# Speaker_Switch_2.net
KiCad netlist of a schematic drawn in EasyEDA Pro
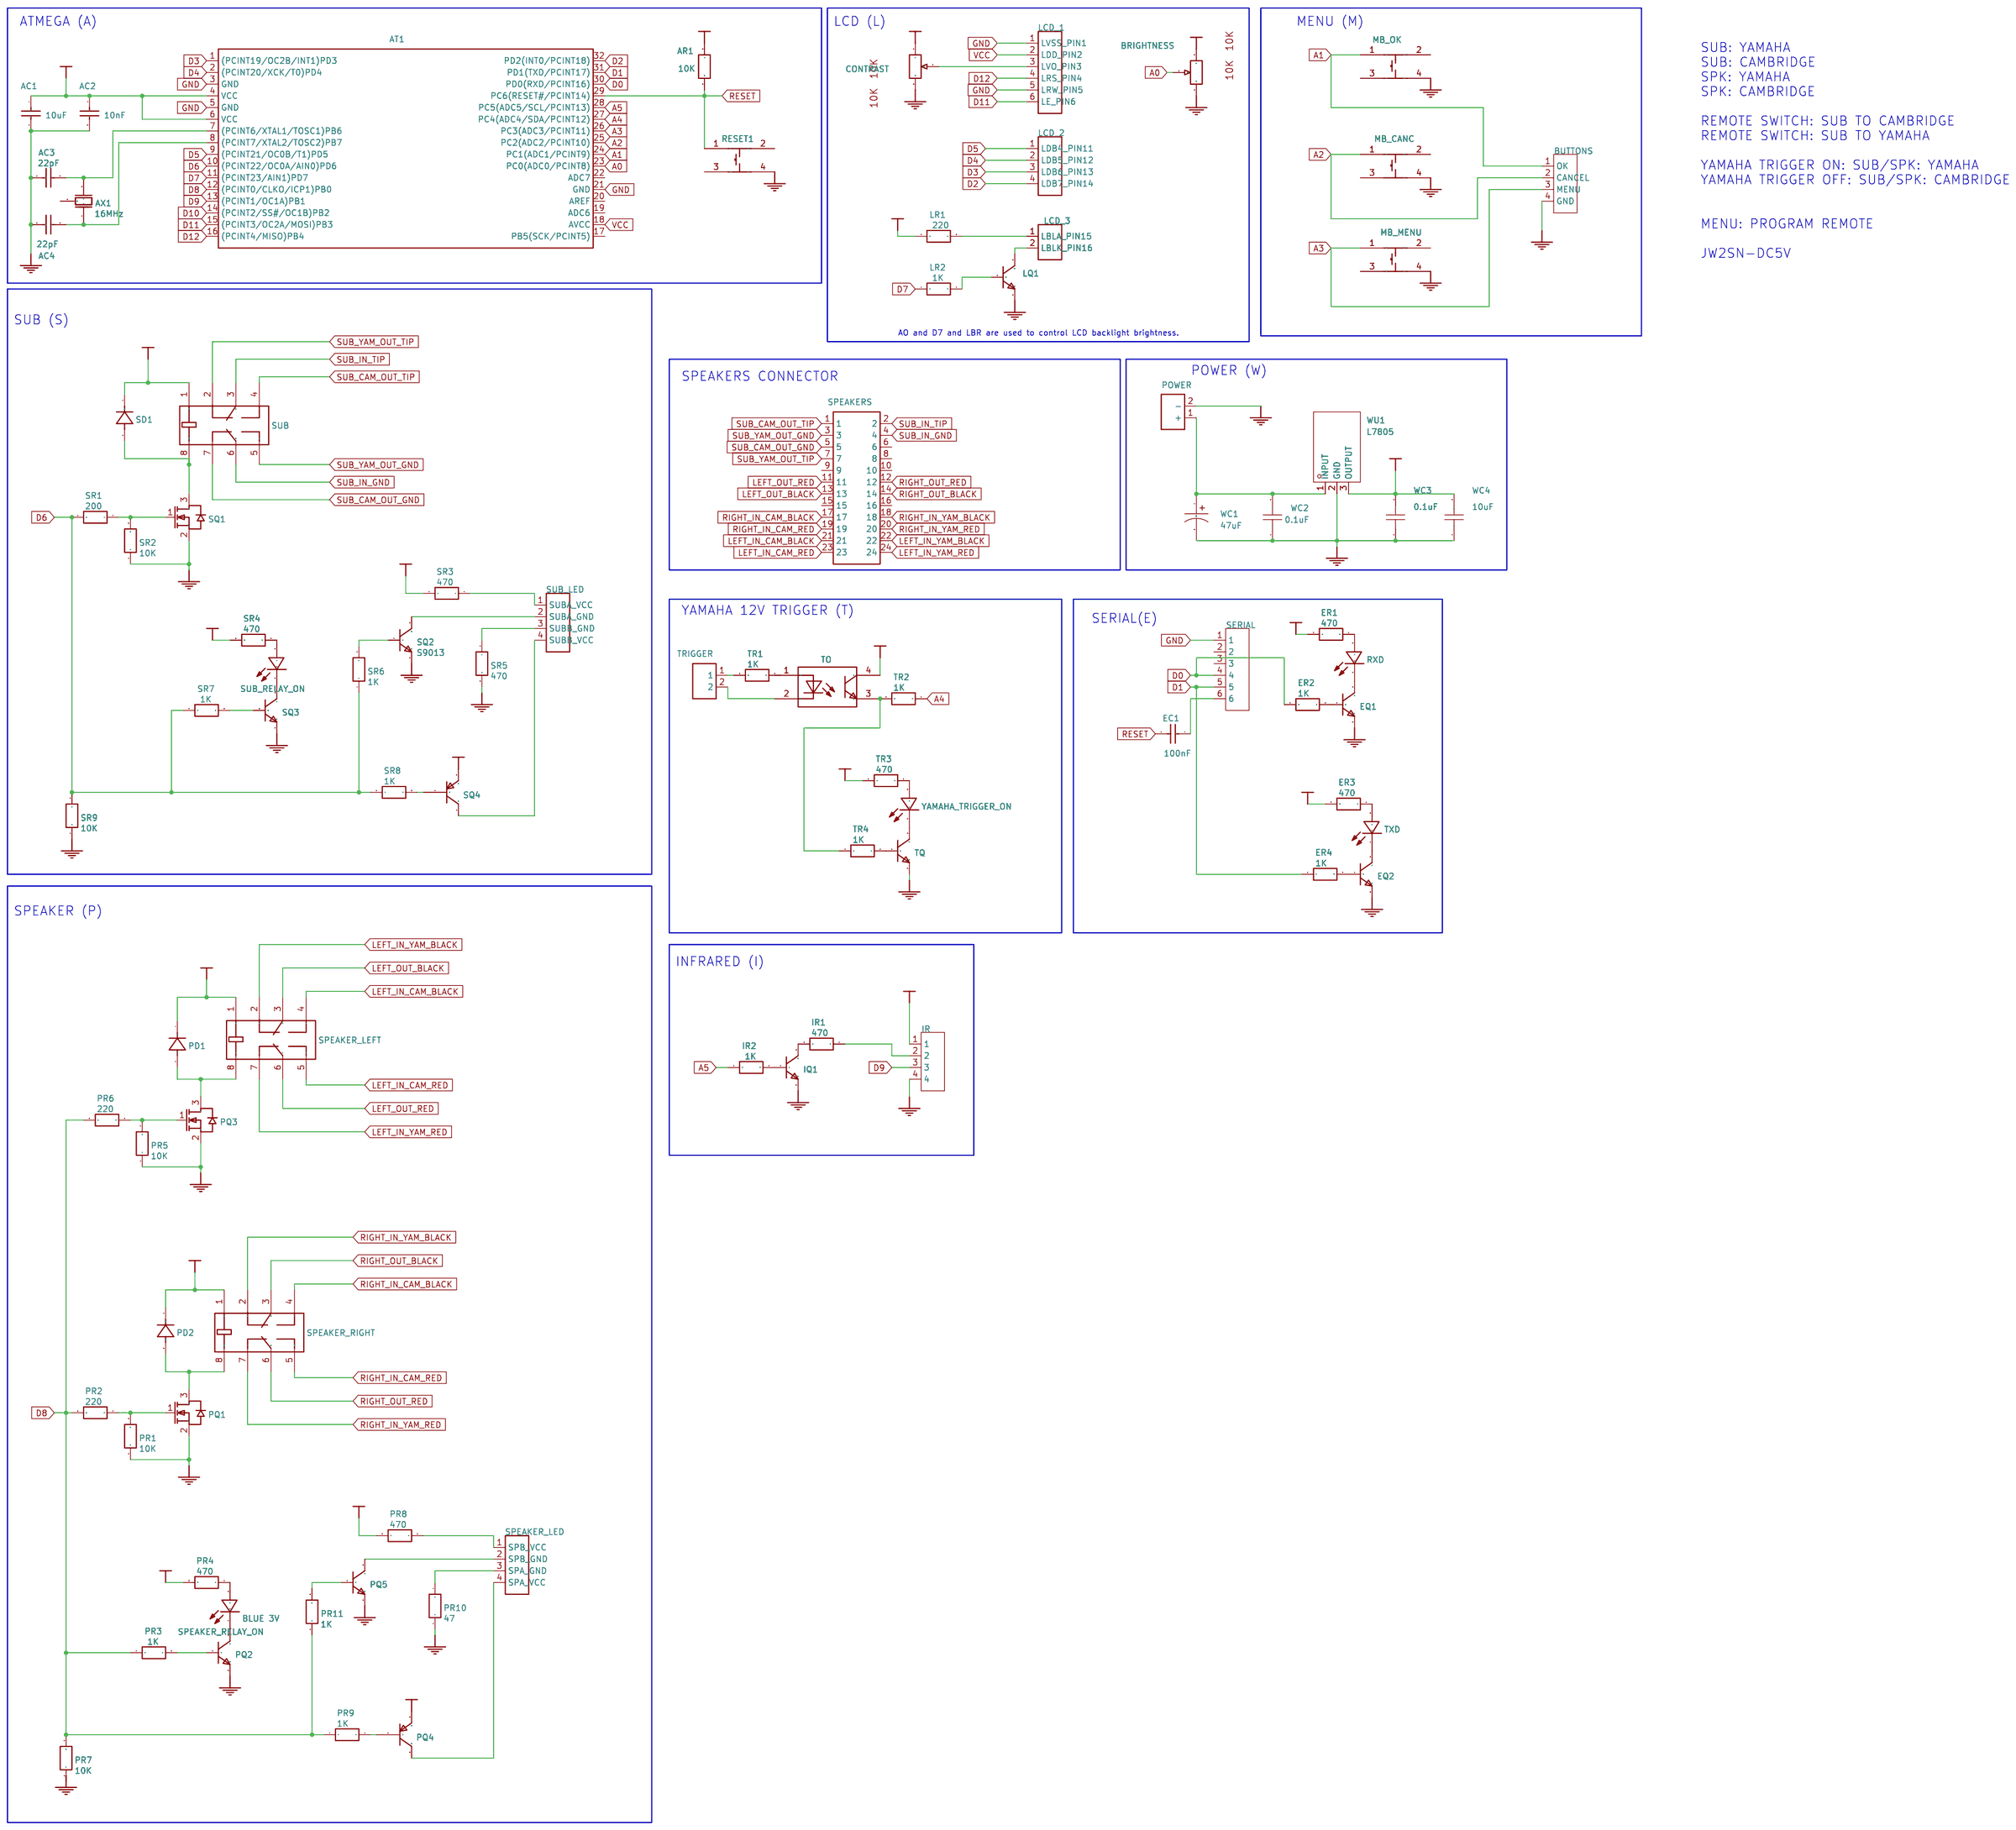
[diagram p0: schematic sheet]

(export (version "E")
  (design (tool "Eeschema 10.0.6"))
  (components
    (comp (ref "AC1")
      (value "10uF")
      (footprint "easyedapro:C0805")
      (fields (field (name "Manufacturer Part") "CC0805KKX7R9BB105") (field (name "Manufacturer") "YAGEO"))
      (libsource (lib "easyedapro") (part "10uF"))
    )
    (comp (ref "AC2")
      (value "10nF")
      (footprint "easyedapro:C0805")
      (fields (field (name "Manufacturer Part") "CC0805KKX7R9BB105") (field (name "Manufacturer") "YAGEO"))
      (libsource (lib "easyedapro") (part "10nF"))
    )
    (comp (ref "AC3")
      (value "22pF")
      (footprint "easyedapro:C0805")
      (fields (field (name "Manufacturer Part") "CC0805KKX7R9BB105") (field (name "Manufacturer") "YAGEO"))
      (libsource (lib "easyedapro") (part "22pF"))
    )
    (comp (ref "AC4")
      (value "22pF")
      (footprint "easyedapro:C0805")
      (fields (field (name "Manufacturer Part") "CC0805KKX7R9BB105") (field (name "Manufacturer") "YAGEO"))
      (libsource (lib "easyedapro") (part "22pF"))
    )
    (comp (ref "AR1")
      (value "10K")
      (footprint "easyedapro:R0805")
      (fields
        (field (name "Manufacturer Part") "WR08X102 JTL")
        (field (name "Manufacturer") "Walsin Tech Corp")
      )
      (libsource (lib "easyedapro") (part "1K"))
    )
    (comp (ref "AT1")
      (value "ATMEGA328P-AU")
      (footprint "easyedapro:TQFP-32_L7.0-W7.0-P0.80-LS9.0-BL")
      (fields (field (name "Manufacturer") "MICROCHIP"))
      (libsource (lib "easyedapro") (part "ATMEGA328P-AU"))
    )
    (comp (ref "AX1")
      (value "16MHz")
      (footprint "easyedapro:OSC-SMD_3P-L3.2-W1.3-P1.2-L")
      (fields
        (field (name "Manufacturer Part") "CSTNE16M0V530000R0")
        (field (name "Manufacturer") "Murata Electronics")
      )
      (libsource (lib "easyedapro") (part "16MHz"))
    )
    (comp (ref "BRIGHTNESS")
      (value "potentiometer")
      (footprint "easyedapro:POTENTIOMETER")
      (libsource (lib "easyedapro") (part "potentiometer"))
    )
    (comp (ref "BUTTONS")
      (value "AXH-4A-11")
      (footprint "easyedapro:CONN-TH_KH-XH-4A-Z")
      (fields (field (name "Manufacturer") "JXTCONN(聚兴泰)"))
      (libsource (lib "easyedapro") (part "AXH-4A-11-BTN"))
    )
    (comp (ref "CONTRAST")
      (value "potentiometer")
      (footprint "easyedapro:POTENTIOMETER")
      (libsource (lib "easyedapro") (part "potentiometer"))
    )
    (comp (ref "EC1")
      (value "100nF")
      (footprint "easyedapro:C0805")
      (fields (field (name "Manufacturer Part") "CC0805KKX7R9BB105") (field (name "Manufacturer") "YAGEO"))
      (libsource (lib "easyedapro") (part "100nF"))
    )
    (comp (ref "EQ1")
      (value "S9013")
      (footprint "easyedapro:SOT-23-3_L2.9-W1.6-P1.90-LS2.8-BR")
      (fields (field (name "Manufacturer Part") "S9013 120-200") (field (name "Manufacturer") "CJ"))
      (libsource (lib "easyedapro") (part "S9013"))
    )
    (comp (ref "EQ2")
      (value "S9013")
      (footprint "easyedapro:SOT-23-3_L2.9-W1.6-P1.90-LS2.8-BR")
      (fields (field (name "Manufacturer Part") "S9013 120-200") (field (name "Manufacturer") "CJ"))
      (libsource (lib "easyedapro") (part "S9013"))
    )
    (comp (ref "ER1")
      (value "470")
      (footprint "easyedapro:R0805")
      (fields
        (field (name "Manufacturer Part") "WR08X102 JTL")
        (field (name "Manufacturer") "Walsin Tech Corp")
      )
      (libsource (lib "easyedapro") (part "220"))
    )
    (comp (ref "ER2")
      (value "1K")
      (footprint "easyedapro:R0805")
      (fields
        (field (name "Manufacturer Part") "WR08X102 JTL")
        (field (name "Manufacturer") "Walsin Tech Corp")
      )
      (libsource (lib "") (part "1K_2"))
    )
    (comp (ref "ER3")
      (value "470")
      (footprint "easyedapro:R0805")
      (fields
        (field (name "Manufacturer Part") "WR08X102 JTL")
        (field (name "Manufacturer") "Walsin Tech Corp")
      )
      (libsource (lib "easyedapro") (part "220"))
    )
    (comp (ref "ER4")
      (value "1K")
      (footprint "easyedapro:R0805")
      (fields
        (field (name "Manufacturer Part") "WR08X102 JTL")
        (field (name "Manufacturer") "Walsin Tech Corp")
      )
      (libsource (lib "") (part "1K_2"))
    )
    (comp (ref "IQ1")
      (value "S9013")
      (footprint "easyedapro:SOT-23-3_L2.9-W1.6-P1.90-LS2.8-BR")
      (fields (field (name "Manufacturer Part") "S9013 120-200") (field (name "Manufacturer") "CJ"))
      (libsource (lib "easyedapro") (part "S9013"))
    )
    (comp (ref "IR")
      (value "AXH-4A-11")
      (footprint "easyedapro:CONN-TH_KH-XH-4A-Z")
      (fields (field (name "Manufacturer") "JXTCONN(聚兴泰)"))
      (libsource (lib "") (part "AXH-4A-11_2"))
    )
    (comp (ref "IR1")
      (value "470")
      (footprint "easyedapro:R0805")
      (fields
        (field (name "Manufacturer Part") "WR08X102 JTL")
        (field (name "Manufacturer") "Walsin Tech Corp")
      )
      (libsource (lib "easyedapro") (part "220"))
    )
    (comp (ref "IR2")
      (value "1K")
      (footprint "easyedapro:R0805")
      (fields
        (field (name "Manufacturer Part") "WR08X102 JTL")
        (field (name "Manufacturer") "Walsin Tech Corp")
      )
      (libsource (lib "") (part "1K_2"))
    )
    (comp (ref "LCD_1")
      (value "XD-XH-6A-G")
      (footprint "easyedapro:CONN-TH_XH-6A")
      (fields (field (name "Manufacturer") "XUNDA(讯答)"))
      (libsource (lib "easyedapro") (part "XD-XH-6A-G"))
    )
    (comp (ref "LCD_2")
      (value "AXH-4A-11")
      (footprint "easyedapro:CONN-TH_KH-XH-4A-Z")
      (fields (field (name "Manufacturer") "JXTCONN(聚兴泰)"))
      (libsource (lib "") (part "AXH-4A-11_3"))
    )
    (comp (ref "LCD_3")
      (value "XH-D-2A")
      (footprint "easyedapro:CONN-TH_XH-2A")
      (fields (field (name "Manufacturer") "DEALON(德艺隆)"))
      (libsource (lib "easyedapro") (part "XH-D-2A"))
    )
    (comp (ref "LQ1")
      (value "S9013")
      (footprint "easyedapro:SOT-23-3_L2.9-W1.6-P1.90-LS2.8-BR")
      (fields (field (name "Manufacturer Part") "S9013 120-200") (field (name "Manufacturer") "CJ"))
      (libsource (lib "easyedapro") (part "S9013"))
    )
    (comp (ref "LR1")
      (value "220")
      (footprint "easyedapro:R0805")
      (fields
        (field (name "Manufacturer Part") "WR08X102 JTL")
        (field (name "Manufacturer") "Walsin Tech Corp")
      )
      (libsource (lib "") (part "220_1"))
    )
    (comp (ref "LR2")
      (value "1K")
      (footprint "easyedapro:R0805")
      (fields
        (field (name "Manufacturer Part") "WR08X102 JTL")
        (field (name "Manufacturer") "Walsin Tech Corp")
      )
      (libsource (lib "") (part "1K_2"))
    )
    (comp (ref "MB_CANC")
      (value "Push Button")
      (footprint "easyedapro:PUSH_BUTTON-SMD_4P")
      (libsource (lib "easyedapro") (part "Push Button"))
    )
    (comp (ref "MB_MENU")
      (value "Push Button")
      (footprint "easyedapro:PUSH_BUTTON-SMD_4P")
      (libsource (lib "easyedapro") (part "Push Button"))
    )
    (comp (ref "MB_OK")
      (value "Push Button")
      (footprint "easyedapro:PUSH_BUTTON-SMD_4P")
      (libsource (lib "easyedapro") (part "Push Button"))
    )
    (comp (ref "PD1")
      (value "S1M_C3011098")
      (footprint "easyedapro:SMA_L4.3-W2.6-LS5.0-RD")
      (fields (field (name "Manufacturer Part") "S1M") (field (name "Manufacturer") "YAGEO"))
      (libsource (lib "easyedapro") (part "S1M_C3011098"))
    )
    (comp (ref "PD2")
      (value "S1M_C3011098")
      (footprint "easyedapro:SMA_L4.3-W2.6-LS5.0-RD")
      (fields (field (name "Manufacturer Part") "S1M") (field (name "Manufacturer") "YAGEO"))
      (libsource (lib "easyedapro") (part "S1M_C3011098"))
    )
    (comp (ref "POWER")
      (value "XH-D-2A")
      (footprint "easyedapro:CONN-TH_XH-2A")
      (fields (field (name "Manufacturer") "DEALON(德艺隆)"))
      (libsource (lib "easyedapro") (part "XH-D-2A-POWER"))
    )
    (comp (ref "PQ1")
      (value "2N7002-G")
      (footprint "easyedapro:SOT-23-3_L2.9-W1.6-P1.90-LS2.8-BR")
      (fields (field (name "Manufacturer") "Diotec Semiconductor"))
      (libsource (lib "easyedapro") (part "2N7002-G"))
    )
    (comp (ref "PQ2")
      (value "S9013")
      (footprint "easyedapro:SOT-23-3_L2.9-W1.6-P1.90-LS2.8-BR")
      (fields (field (name "Manufacturer Part") "S9013 120-200") (field (name "Manufacturer") "CJ"))
      (libsource (lib "easyedapro") (part "S9013"))
    )
    (comp (ref "PQ3")
      (value "2N7002-G")
      (footprint "easyedapro:SOT-23-3_L2.9-W1.6-P1.90-LS2.8-BR")
      (fields (field (name "Manufacturer") "Diotec Semiconductor"))
      (libsource (lib "easyedapro") (part "2N7002-G"))
    )
    (comp (ref "PQ4")
      (value "S8550")
      (footprint "easyedapro:SOT-23-3_L2.9-W1.3-P1.90-LS2.4-BR")
      (fields (field (name "Manufacturer") "CBI(创基)"))
      (libsource (lib "easyedapro") (part "S8550"))
    )
    (comp (ref "PQ5")
      (value "S9013")
      (footprint "easyedapro:SOT-23-3_L2.9-W1.6-P1.90-LS2.8-BR")
      (fields (field (name "Manufacturer Part") "S9013 120-200") (field (name "Manufacturer") "CJ"))
      (libsource (lib "easyedapro") (part "S9013"))
    )
    (comp (ref "PR1")
      (value "10K")
      (footprint "easyedapro:R0805")
      (fields
        (field (name "Manufacturer Part") "WR08X102 JTL")
        (field (name "Manufacturer") "Walsin Tech Corp")
      )
      (libsource (lib "easyedapro") (part "10K"))
    )
    (comp (ref "PR2")
      (value "220")
      (footprint "easyedapro:R0805")
      (fields
        (field (name "Manufacturer Part") "WR08X102 JTL")
        (field (name "Manufacturer") "Walsin Tech Corp")
      )
      (libsource (lib "easyedapro") (part "220"))
    )
    (comp (ref "PR3")
      (value "1K")
      (footprint "easyedapro:R0805")
      (fields
        (field (name "Manufacturer Part") "WR08X102 JTL")
        (field (name "Manufacturer") "Walsin Tech Corp")
      )
      (libsource (lib "") (part "1K_2"))
    )
    (comp (ref "PR4")
      (value "470")
      (footprint "easyedapro:R0805")
      (fields
        (field (name "Manufacturer Part") "WR08X102 JTL")
        (field (name "Manufacturer") "Walsin Tech Corp")
      )
      (libsource (lib "easyedapro") (part "220"))
    )
    (comp (ref "PR5")
      (value "10K")
      (footprint "easyedapro:R0805")
      (fields
        (field (name "Manufacturer Part") "WR08X102 JTL")
        (field (name "Manufacturer") "Walsin Tech Corp")
      )
      (libsource (lib "easyedapro") (part "10K"))
    )
    (comp (ref "PR6")
      (value "220")
      (footprint "easyedapro:R0805")
      (fields
        (field (name "Manufacturer Part") "WR08X102 JTL")
        (field (name "Manufacturer") "Walsin Tech Corp")
      )
      (libsource (lib "easyedapro") (part "220"))
    )
    (comp (ref "PR7")
      (value "10K")
      (footprint "easyedapro:R0805")
      (fields
        (field (name "Manufacturer Part") "WR08X102 JTL")
        (field (name "Manufacturer") "Walsin Tech Corp")
      )
      (libsource (lib "easyedapro") (part "10K"))
    )
    (comp (ref "PR8")
      (value "470")
      (footprint "easyedapro:R0805")
      (fields
        (field (name "Manufacturer Part") "WR08X102 JTL")
        (field (name "Manufacturer") "Walsin Tech Corp")
      )
      (libsource (lib "easyedapro") (part "220"))
    )
    (comp (ref "PR9")
      (value "1K")
      (footprint "easyedapro:R0805")
      (fields
        (field (name "Manufacturer Part") "WR08X102 JTL")
        (field (name "Manufacturer") "Walsin Tech Corp")
      )
      (libsource (lib "") (part "1K_2"))
    )
    (comp (ref "PR10")
      (value "47")
      (footprint "easyedapro:R0805")
      (fields
        (field (name "Manufacturer Part") "WR08X102 JTL")
        (field (name "Manufacturer") "Walsin Tech Corp")
      )
      (libsource (lib "") (part "220_2"))
    )
    (comp (ref "PR11")
      (value "1K")
      (footprint "easyedapro:R0805")
      (fields
        (field (name "Manufacturer Part") "WR08X102 JTL")
        (field (name "Manufacturer") "Walsin Tech Corp")
      )
      (libsource (lib "easyedapro") (part "1K"))
    )
    (comp (ref "RESET1")
      (value "Push Button")
      (footprint "easyedapro:PUSH_BUTTON-SMD_4P")
      (libsource (lib "easyedapro") (part "Push Button"))
    )
    (comp (ref "RXD")
      (value "BLUE 3V")
      (footprint "easyedapro:LED0805-RD")
      (fields
        (field (name "Manufacturer Part") "FC-1608YOXK-600H08")
        (field (name "Manufacturer") "NATIONSTAR")
      )
      (libsource (lib "easyedapro") (part "BLUE 3V"))
    )
    (comp (ref "SD1")
      (value "S1M_C3011098")
      (footprint "easyedapro:SMA_L4.3-W2.6-LS5.0-RD")
      (fields (field (name "Manufacturer Part") "S1M") (field (name "Manufacturer") "YAGEO"))
      (libsource (lib "easyedapro") (part "S1M_C3011098"))
    )
    (comp (ref "SERIAL")
      (value "2.54-1*6")
      (footprint "easyedapro:HDR-TH_6P-P2.54-V-M")
      (fields (field (name "Manufacturer") "ZHOURI(洲日)"))
      (libsource (lib "easyedapro") (part "2.54-1*6"))
    )
    (comp (ref "SPEAKER_LED")
      (value "AXH-4A-11")
      (footprint "easyedapro:CONN-TH_KH-XH-4A-Z")
      (fields (field (name "Manufacturer") "JXTCONN(聚兴泰)"))
      (libsource (lib "easyedapro") (part "AXH-4A-11"))
    )
    (comp (ref "SPEAKER_LEFT")
      (value "JW2SN-DC5V")
      (footprint "easyedapro:RELAY-TH_JW2SN-DCXXV")
      (fields (field (name "Manufacturer") "PANASONIC(松下)"))
      (libsource (lib "easyedapro") (part "JW2SN-DC5V"))
    )
    (comp (ref "SPEAKER_RELAY_ON")
      (value "BLUE 3V")
      (footprint "easyedapro:LED0805-RD")
      (fields
        (field (name "Manufacturer Part") "FC-1608YOXK-600H08")
        (field (name "Manufacturer") "NATIONSTAR")
      )
      (libsource (lib "easyedapro") (part "BLUE 3V"))
    )
    (comp (ref "SPEAKER_RIGHT")
      (value "JW2SN-DC5V")
      (footprint "easyedapro:RELAY-TH_JW2SN-DCXXV")
      (fields (field (name "Manufacturer") "PANASONIC(松下)"))
      (libsource (lib "easyedapro") (part "JW2SN-DC5V"))
    )
    (comp (ref "SQ1")
      (value "2N7002-G")
      (footprint "easyedapro:SOT-23-3_L2.9-W1.6-P1.90-LS2.8-BR")
      (fields (field (name "Manufacturer") "Diotec Semiconductor"))
      (libsource (lib "easyedapro") (part "2N7002-G"))
    )
    (comp (ref "SQ2")
      (value "S9013")
      (footprint "easyedapro:SOT-23-3_L2.9-W1.6-P1.90-LS2.8-BR")
      (fields (field (name "Manufacturer Part") "S9013 120-200") (field (name "Manufacturer") "CJ"))
      (libsource (lib "easyedapro") (part "S9013"))
    )
    (comp (ref "SQ3")
      (value "S9013")
      (footprint "easyedapro:SOT-23-3_L2.9-W1.6-P1.90-LS2.8-BR")
      (fields (field (name "Manufacturer Part") "S9013 120-200") (field (name "Manufacturer") "CJ"))
      (libsource (lib "easyedapro") (part "S9013"))
    )
    (comp (ref "SQ4")
      (value "S8550")
      (footprint "easyedapro:SOT-23-3_L2.9-W1.3-P1.90-LS2.4-BR")
      (fields (field (name "Manufacturer") "CBI(创基)"))
      (libsource (lib "easyedapro") (part "S8550"))
    )
    (comp (ref "SR1")
      (value "200")
      (footprint "easyedapro:R0805")
      (fields
        (field (name "Manufacturer Part") "WR08X102 JTL")
        (field (name "Manufacturer") "Walsin Tech Corp")
      )
      (libsource (lib "easyedapro") (part "220"))
    )
    (comp (ref "SR2")
      (value "10K")
      (footprint "easyedapro:R0805")
      (fields
        (field (name "Manufacturer Part") "WR08X102 JTL")
        (field (name "Manufacturer") "Walsin Tech Corp")
      )
      (libsource (lib "easyedapro") (part "10K"))
    )
    (comp (ref "SR3")
      (value "470")
      (footprint "easyedapro:R0805")
      (fields
        (field (name "Manufacturer Part") "WR08X102 JTL")
        (field (name "Manufacturer") "Walsin Tech Corp")
      )
      (libsource (lib "") (part "1K_1"))
    )
    (comp (ref "SR4")
      (value "470")
      (footprint "easyedapro:R0805")
      (fields
        (field (name "Manufacturer Part") "WR08X102 JTL")
        (field (name "Manufacturer") "Walsin Tech Corp")
      )
      (libsource (lib "easyedapro") (part "220"))
    )
    (comp (ref "SR5")
      (value "470")
      (footprint "easyedapro:R0805")
      (fields
        (field (name "Manufacturer Part") "WR08X102 JTL")
        (field (name "Manufacturer") "Walsin Tech Corp")
      )
      (libsource (lib "easyedapro") (part "300"))
    )
    (comp (ref "SR6")
      (value "1K")
      (footprint "easyedapro:R0805")
      (fields
        (field (name "Manufacturer Part") "WR08X102 JTL")
        (field (name "Manufacturer") "Walsin Tech Corp")
      )
      (libsource (lib "easyedapro") (part "1K"))
    )
    (comp (ref "SR7")
      (value "1K")
      (footprint "easyedapro:R0805")
      (fields
        (field (name "Manufacturer Part") "WR08X102 JTL")
        (field (name "Manufacturer") "Walsin Tech Corp")
      )
      (libsource (lib "") (part "1K_2"))
    )
    (comp (ref "SR8")
      (value "1K")
      (footprint "easyedapro:R0805")
      (fields
        (field (name "Manufacturer Part") "WR08X102 JTL")
        (field (name "Manufacturer") "Walsin Tech Corp")
      )
      (libsource (lib "") (part "1K_2"))
    )
    (comp (ref "SR9")
      (value "10K")
      (footprint "easyedapro:R0805")
      (fields
        (field (name "Manufacturer Part") "WR08X102 JTL")
        (field (name "Manufacturer") "Walsin Tech Corp")
      )
      (libsource (lib "easyedapro") (part "10K"))
    )
    (comp (ref "SUB")
      (value "JW2SN-DC5V")
      (footprint "easyedapro:RELAY-TH_JW2SN-DCXXV")
      (fields (field (name "Manufacturer") "PANASONIC(松下)"))
      (libsource (lib "easyedapro") (part "JW2SN-DC5V"))
    )
    (comp (ref "SUB_LED")
      (value "AXH-4A-11")
      (footprint "easyedapro:CONN-TH_KH-XH-4A-Z")
      (fields (field (name "Manufacturer") "JXTCONN(聚兴泰)"))
      (libsource (lib "") (part "AXH-4A-11_1"))
    )
    (comp (ref "SUB_RELAY_ON")
      (value "BLUE 3V")
      (footprint "easyedapro:LED0805-RD")
      (fields
        (field (name "Manufacturer Part") "FC-1608YOXK-600H08")
        (field (name "Manufacturer") "NATIONSTAR")
      )
      (libsource (lib "easyedapro") (part "BLUE 3V"))
    )
    (comp (ref "TO")
      (value "LTV-817S-TA1-C")
      (footprint "easyedapro:OPTO-SMD-4_L4.6-W6.5-P2.54-LS10.3-BL")
      (fields (field (name "Manufacturer") "LITEON(光宝)"))
      (libsource (lib "easyedapro") (part "LTV-817S-TA1-C"))
    )
    (comp (ref "TQ")
      (value "S9013")
      (footprint "easyedapro:SOT-23-3_L2.9-W1.6-P1.90-LS2.8-BR")
      (fields (field (name "Manufacturer Part") "S9013 120-200") (field (name "Manufacturer") "CJ"))
      (libsource (lib "easyedapro") (part "S9013"))
    )
    (comp (ref "TR1")
      (value "1K")
      (footprint "easyedapro:R0805")
      (fields
        (field (name "Manufacturer Part") "WR08X102 JTL")
        (field (name "Manufacturer") "Walsin Tech Corp")
      )
      (libsource (lib "") (part "1K_1"))
    )
    (comp (ref "TR2")
      (value "1K")
      (footprint "easyedapro:R0805")
      (fields
        (field (name "Manufacturer Part") "WR08X102 JTL")
        (field (name "Manufacturer") "Walsin Tech Corp")
      )
      (libsource (lib "") (part "1K_1"))
    )
    (comp (ref "TR3")
      (value "470")
      (footprint "easyedapro:R0805")
      (fields
        (field (name "Manufacturer Part") "WR08X102 JTL")
        (field (name "Manufacturer") "Walsin Tech Corp")
      )
      (libsource (lib "easyedapro") (part "220"))
    )
    (comp (ref "TR4")
      (value "1K")
      (footprint "easyedapro:R0805")
      (fields
        (field (name "Manufacturer Part") "WR08X102 JTL")
        (field (name "Manufacturer") "Walsin Tech Corp")
      )
      (libsource (lib "") (part "1K_2"))
    )
    (comp (ref "TRIGGER")
      (value "XH-2A_C3012117")
      (footprint "easyedapro:CONN-TH_XH-2A")
      (fields (field (name "Manufacturer Part") "XH-2A") (field (name "Manufacturer") "HCTL(华灿天禄)"))
      (libsource (lib "easyedapro") (part "XH-2A_C3012117"))
    )
    (comp (ref "TXD")
      (value "BLUE 3V")
      (footprint "easyedapro:LED0805-RD")
      (fields
        (field (name "Manufacturer Part") "FC-1608YOXK-600H08")
        (field (name "Manufacturer") "NATIONSTAR")
      )
      (libsource (lib "easyedapro") (part "BLUE 3V"))
    )
    (comp (ref "U1")
      (value "SPEAKERS")
      (footprint "easyedapro:CONN-TH_C4255WV-2X12P")
      (fields (field (name "Manufacturer Part") "ATX-24PIN"))
      (libsource (lib "easyedapro") (part "SPEAKERS"))
    )
    (comp (ref "WC1")
      (value "47uF")
      (footprint "easyedapro:CAP-TH_BD6.3-P2.5-D0.5")
      (fields (field (name "Manufacturer Part") "50V47uF CD288") (field (name "Manufacturer") "HRK(鸿瑞凯电子)"))
      (libsource (lib "easyedapro") (part "50V47UF CD288"))
    )
    (comp (ref "WC2")
      (value "0.1uF")
      (footprint "easyedapro:C0805")
      (description "Capacitance:100nF Tolerance:±10% Tolerance:±10% Voltage Rating:50V Temperature Coefficient:-")
      (fields
        (field (name "Manufacturer Part") "CT41G-0805-2X1-50V-0.1uF-K(N)")
        (field (name "Manufacturer") "TORCH(火炬)")
      )
      (libsource (lib "easyedapro") (part "CT41G-0805-2X1-50V-0.1UF-K(N)"))
    )
    (comp (ref "WC3")
      (value "0.1uF")
      (footprint "easyedapro:C0805")
      (description "Capacitance:100nF Tolerance:±10% Tolerance:±10% Voltage Rating:50V Temperature Coefficient:-")
      (fields
        (field (name "Manufacturer Part") "CT41G-0805-2X1-50V-0.1uF-K(N)")
        (field (name "Manufacturer") "TORCH(火炬)")
      )
      (libsource (lib "easyedapro") (part "CT41G-0805-2X1-50V-0.1UF-K(N)"))
    )
    (comp (ref "WC4")
      (value "10uF")
      (footprint "easyedapro:C0805")
      (description "Capacitance:100nF Tolerance:±10% Tolerance:±10% Voltage Rating:50V Temperature Coefficient:-")
      (fields
        (field (name "Manufacturer Part") "CT41G-0805-2X1-50V-0.1uF-K(N)")
        (field (name "Manufacturer") "TORCH(火炬)")
      )
      (libsource (lib "easyedapro") (part "CT41G-0805-2X1-50V-0.1UF-K(N)"))
    )
    (comp (ref "WU1")
      (value "L7805")
      (footprint "easyedapro:TO-220-3_L10.0-W4.5-P2.54-L")
      (fields (field (name "Manufacturer") "OSEN(欧芯)"))
      (libsource (lib "easyedapro") (part "L7805_C22378639"))
    )
    (comp (ref "YAMAHA_TRIGGER_ON")
      (value "BLUE 3V")
      (footprint "easyedapro:LED0805-RD")
      (fields
        (field (name "Manufacturer Part") "FC-1608YOXK-600H08")
        (field (name "Manufacturer") "NATIONSTAR")
      )
      (libsource (lib "easyedapro") (part "BLUE 3V"))
    )
  )
  (nets
    (net (code "1") (name "A0") (class "Default")
      (node (ref "AT1") (pin "23") (pinfunction "PC0(ADC0/PCINT8)_23") (pintype "unspecified"))
      (node (ref "BRIGHTNESS") (pin "2") (pinfunction "2_2") (pintype "input"))
    )
    (net (code "2") (name "A1") (class "Default")
      (node (ref "AT1") (pin "24") (pinfunction "PC1(ADC1/PCINT9)_24") (pintype "unspecified"))
      (node (ref "BUTTONS") (pin "1") (pinfunction "OK_1") (pintype "unspecified"))
      (node (ref "MB_OK") (pin "1") (pinfunction "1_1") (pintype "unspecified"))
    )
    (net (code "3") (name "A2") (class "Default")
      (node (ref "AT1") (pin "25") (pinfunction "PC2(ADC2/PCINT10)_25") (pintype "unspecified"))
      (node (ref "BUTTONS") (pin "2") (pinfunction "CANCEL_2") (pintype "unspecified"))
      (node (ref "MB_CANC") (pin "1") (pinfunction "1_1") (pintype "unspecified"))
    )
    (net (code "4") (name "A3") (class "Default")
      (node (ref "AT1") (pin "26") (pinfunction "PC3(ADC3/PCINT11)_26") (pintype "unspecified"))
      (node (ref "BUTTONS") (pin "3") (pinfunction "MENU_3") (pintype "unspecified"))
      (node (ref "MB_MENU") (pin "1") (pinfunction "1_1") (pintype "unspecified"))
    )
    (net (code "5") (name "A4") (class "Default")
      (node (ref "AT1") (pin "27") (pinfunction "PC4(ADC4/SDA/PCINT12)_27") (pintype "unspecified"))
      (node (ref "TR2") (pin "1") (pinfunction "1_1") (pintype "unspecified"))
    )
    (net (code "6") (name "A5") (class "Default")
      (node (ref "AT1") (pin "28") (pinfunction "PC5(ADC5/SCL/PCINT13)_28") (pintype "unspecified"))
      (node (ref "IR2") (pin "1") (pinfunction "1_1") (pintype "unspecified"))
    )
    (net (code "7") (name "D0") (class "Default")
      (node (ref "AT1") (pin "30") (pinfunction "PD0(RXD/PCINT16)_30") (pintype "unspecified"))
      (node (ref "ER2") (pin "1") (pinfunction "1_1") (pintype "unspecified"))
      (node (ref "SERIAL") (pin "4") (pinfunction "4_4") (pintype "unspecified"))
    )
    (net (code "8") (name "D1") (class "Default")
      (node (ref "AT1") (pin "31") (pinfunction "PD1(TXD/PCINT17)_31") (pintype "unspecified"))
      (node (ref "ER4") (pin "1") (pinfunction "1_1") (pintype "unspecified"))
      (node (ref "SERIAL") (pin "5") (pinfunction "5_5") (pintype "unspecified"))
    )
    (net (code "9") (name "D2") (class "Default")
      (node (ref "AT1") (pin "32") (pinfunction "PD2(INT0/PCINT18)_32") (pintype "unspecified"))
      (node (ref "LCD_2") (pin "4") (pinfunction "LDB7_PIN14_4") (pintype "unspecified"))
    )
    (net (code "10") (name "D3") (class "Default")
      (node (ref "AT1") (pin "1") (pinfunction "(PCINT19/OC2B/INT1)PD3_1") (pintype "unspecified"))
      (node (ref "LCD_2") (pin "3") (pinfunction "LDB6_PIN13_3") (pintype "unspecified"))
    )
    (net (code "11") (name "D4") (class "Default")
      (node (ref "AT1") (pin "2") (pinfunction "(PCINT20/XCK/T0)PD4_2") (pintype "unspecified"))
      (node (ref "LCD_2") (pin "2") (pinfunction "LDB5_PIN12_2") (pintype "unspecified"))
    )
    (net (code "12") (name "D5") (class "Default")
      (node (ref "AT1") (pin "9") (pinfunction "(PCINT21/OC0B/T1)PD5_9") (pintype "unspecified"))
      (node (ref "LCD_2") (pin "1") (pinfunction "LDB4_PIN11_1") (pintype "unspecified"))
    )
    (net (code "13") (name "D6") (class "Default")
      (node (ref "AT1") (pin "10") (pinfunction "(PCINT22/OC0A/AIN0)PD6_10") (pintype "unspecified"))
      (node (ref "SR1") (pin "2") (pinfunction "2_2") (pintype "unspecified"))
      (node (ref "SR6") (pin "1") (pinfunction "1_1") (pintype "unspecified"))
      (node (ref "SR7") (pin "1") (pinfunction "1_1") (pintype "unspecified"))
      (node (ref "SR8") (pin "1") (pinfunction "1_1") (pintype "unspecified"))
      (node (ref "SR9") (pin "2") (pinfunction "2_2") (pintype "unspecified"))
    )
    (net (code "14") (name "D7") (class "Default")
      (node (ref "AT1") (pin "11") (pinfunction "(PCINT23/AIN1)PD7_11") (pintype "unspecified"))
      (node (ref "LR2") (pin "1") (pinfunction "1_1") (pintype "unspecified"))
    )
    (net (code "15") (name "D8") (class "Default")
      (node (ref "AT1") (pin "12") (pinfunction "(PCINT0/CLKO/ICP1)PB0_12") (pintype "unspecified"))
      (node (ref "PR11") (pin "1") (pinfunction "1_1") (pintype "unspecified"))
      (node (ref "PR2") (pin "2") (pinfunction "2_2") (pintype "unspecified"))
      (node (ref "PR3") (pin "1") (pinfunction "1_1") (pintype "unspecified"))
      (node (ref "PR6") (pin "2") (pinfunction "2_2") (pintype "unspecified"))
      (node (ref "PR7") (pin "2") (pinfunction "2_2") (pintype "unspecified"))
      (node (ref "PR9") (pin "1") (pinfunction "1_1") (pintype "unspecified"))
    )
    (net (code "16") (name "D9") (class "Default")
      (node (ref "AT1") (pin "13") (pinfunction "(PCINT1/OC1A)PB1_13") (pintype "unspecified"))
      (node (ref "IR") (pin "3") (pinfunction "3_3") (pintype "unspecified"))
    )
    (net (code "17") (name "D10") (class "Default")
      (node (ref "AT1") (pin "14") (pinfunction "(PCINT2/SS#/OC1B)PB2_14") (pintype "unspecified"))
    )
    (net (code "18") (name "D11") (class "Default")
      (node (ref "AT1") (pin "15") (pinfunction "(PCINT3/OC2A/MOSI)PB3_15") (pintype "unspecified"))
      (node (ref "LCD_1") (pin "6") (pinfunction "LE_PIN6_6") (pintype "unspecified"))
    )
    (net (code "19") (name "D12") (class "Default")
      (node (ref "AT1") (pin "16") (pinfunction "(PCINT4/MISO)PB4_16") (pintype "unspecified"))
      (node (ref "LCD_1") (pin "4") (pinfunction "LRS_PIN4_4") (pintype "unspecified"))
    )
    (net (code "20") (name "GND") (class "Default")
      (node (ref "AC1") (pin "2") (pinfunction "2_2") (pintype "input"))
      (node (ref "AC2") (pin "2") (pinfunction "2_2") (pintype "input"))
      (node (ref "AC3") (pin "1") (pinfunction "1_1") (pintype "input"))
      (node (ref "AC4") (pin "1") (pinfunction "1_1") (pintype "input"))
      (node (ref "AT1") (pin "21") (pinfunction "GND_21") (pintype "unspecified"))
      (node (ref "AT1") (pin "3") (pinfunction "GND_3") (pintype "unspecified"))
      (node (ref "AT1") (pin "5") (pinfunction "GND_5") (pintype "unspecified"))
      (node (ref "BRIGHTNESS") (pin "1") (pinfunction "1_1") (pintype "input"))
      (node (ref "BUTTONS") (pin "4") (pinfunction "GND_4") (pintype "unspecified"))
      (node (ref "CONTRAST") (pin "3") (pinfunction "3_3") (pintype "input"))
      (node (ref "EQ1") (pin "2") (pinfunction "2_2") (pintype "input"))
      (node (ref "EQ2") (pin "2") (pinfunction "2_2") (pintype "input"))
      (node (ref "IQ1") (pin "2") (pinfunction "2_2") (pintype "input"))
      (node (ref "IR") (pin "4") (pinfunction "4_4") (pintype "unspecified"))
      (node (ref "LCD_1") (pin "1") (pinfunction "LVSS_PIN1_1") (pintype "unspecified"))
      (node (ref "LCD_1") (pin "5") (pinfunction "LRW_PIN5_5") (pintype "unspecified"))
      (node (ref "LQ1") (pin "2") (pinfunction "2_2") (pintype "input"))
      (node (ref "MB_CANC") (pin "4") (pinfunction "4_4") (pintype "unspecified"))
      (node (ref "MB_MENU") (pin "4") (pinfunction "4_4") (pintype "unspecified"))
      (node (ref "MB_OK") (pin "4") (pinfunction "4_4") (pintype "unspecified"))
      (node (ref "POWER") (pin "2") (pinfunction "-_2") (pintype "unspecified"))
      (node (ref "PQ1") (pin "2") (pinfunction "S_2") (pintype "unspecified"))
      (node (ref "PQ2") (pin "2") (pinfunction "2_2") (pintype "input"))
      (node (ref "PQ3") (pin "2") (pinfunction "S_2") (pintype "unspecified"))
      (node (ref "PQ5") (pin "2") (pinfunction "2_2") (pintype "input"))
      (node (ref "PR1") (pin "1") (pinfunction "1_1") (pintype "unspecified"))
      (node (ref "PR10") (pin "2") (pinfunction "2_2") (pintype "unspecified"))
      (node (ref "PR5") (pin "1") (pinfunction "1_1") (pintype "unspecified"))
      (node (ref "PR7") (pin "1") (pinfunction "1_1") (pintype "unspecified"))
      (node (ref "RESET1") (pin "4") (pinfunction "4_4") (pintype "unspecified"))
      (node (ref "SERIAL") (pin "1") (pinfunction "1_1") (pintype "unspecified"))
      (node (ref "SQ1") (pin "2") (pinfunction "S_2") (pintype "unspecified"))
      (node (ref "SQ2") (pin "2") (pinfunction "2_2") (pintype "input"))
      (node (ref "SQ3") (pin "2") (pinfunction "2_2") (pintype "input"))
      (node (ref "SR2") (pin "1") (pinfunction "1_1") (pintype "unspecified"))
      (node (ref "SR5") (pin "2") (pinfunction "2_2") (pintype "unspecified"))
      (node (ref "SR9") (pin "1") (pinfunction "1_1") (pintype "unspecified"))
      (node (ref "TQ") (pin "2") (pinfunction "2_2") (pintype "input"))
      (node (ref "WC1") (pin "2") (pinfunction "2_2") (pintype "unspecified"))
      (node (ref "WC2") (pin "1") (pinfunction "1_1") (pintype "unspecified"))
      (node (ref "WC3") (pin "1") (pinfunction "1_1") (pintype "unspecified"))
      (node (ref "WC4") (pin "1") (pinfunction "1_1") (pintype "unspecified"))
      (node (ref "WU1") (pin "2") (pinfunction "GND_2") (pintype "unspecified"))
    )
    (net (code "21") (name "LEFT_IN_CAM_BLACK") (class "Default")
      (node (ref "SPEAKER_LEFT") (pin "4") (pinfunction "4_4") (pintype "input"))
      (node (ref "U1") (pin "21") (pinfunction "21_21") (pintype "unspecified"))
    )
    (net (code "22") (name "LEFT_IN_CAM_RED") (class "Default")
      (node (ref "SPEAKER_LEFT") (pin "5") (pinfunction "5_5") (pintype "input"))
      (node (ref "U1") (pin "23") (pinfunction "23_23") (pintype "unspecified"))
    )
    (net (code "23") (name "LEFT_IN_YAM_BLACK") (class "Default")
      (node (ref "SPEAKER_LEFT") (pin "2") (pinfunction "2_2") (pintype "input"))
      (node (ref "U1") (pin "22") (pinfunction "22_22") (pintype "unspecified"))
    )
    (net (code "24") (name "LEFT_IN_YAM_RED") (class "Default")
      (node (ref "SPEAKER_LEFT") (pin "7") (pinfunction "7_7") (pintype "input"))
      (node (ref "U1") (pin "24") (pinfunction "24_24") (pintype "unspecified"))
    )
    (net (code "25") (name "LEFT_OUT_BLACK") (class "Default")
      (node (ref "SPEAKER_LEFT") (pin "3") (pinfunction "3_3") (pintype "input"))
      (node (ref "U1") (pin "13") (pinfunction "13_13") (pintype "unspecified"))
    )
    (net (code "26") (name "LEFT_OUT_RED") (class "Default")
      (node (ref "SPEAKER_LEFT") (pin "6") (pinfunction "6_6") (pintype "input"))
      (node (ref "U1") (pin "11") (pinfunction "11_11") (pintype "unspecified"))
    )
    (net (code "27") (name "Net-(AT1-(PCINT6{slash}XTAL1{slash}TOSC1)PB6)") (class "Default")
      (node (ref "AC3") (pin "2") (pinfunction "2_2") (pintype "input"))
      (node (ref "AT1") (pin "7") (pinfunction "(PCINT6/XTAL1/TOSC1)PB6_7") (pintype "unspecified"))
      (node (ref "AX1") (pin "3") (pinfunction "OSC2_3") (pintype "input"))
    )
    (net (code "28") (name "Net-(AT1-(PCINT7{slash}XTAL2{slash}TOSC2)PB7)") (class "Default")
      (node (ref "AC4") (pin "2") (pinfunction "2_2") (pintype "input"))
      (node (ref "AT1") (pin "8") (pinfunction "(PCINT7/XTAL2/TOSC2)PB7_8") (pintype "unspecified"))
      (node (ref "AX1") (pin "1") (pinfunction "OSC1_1") (pintype "input"))
    )
    (net (code "29") (name "Net-(EC1-Pad1)") (class "Default")
      (node (ref "EC1") (pin "1") (pinfunction "1_1") (pintype "input"))
      (node (ref "SERIAL") (pin "6") (pinfunction "6_6") (pintype "unspecified"))
    )
    (net (code "30") (name "Net-(EQ1-Pad1)") (class "Default")
      (node (ref "EQ1") (pin "1") (pinfunction "1_1") (pintype "input"))
      (node (ref "ER2") (pin "2") (pinfunction "2_2") (pintype "unspecified"))
    )
    (net (code "31") (name "Net-(EQ2-Pad1)") (class "Default")
      (node (ref "EQ2") (pin "1") (pinfunction "1_1") (pintype "input"))
      (node (ref "ER4") (pin "2") (pinfunction "2_2") (pintype "unspecified"))
    )
    (net (code "32") (name "Net-(IQ1-Pad1)") (class "Default")
      (node (ref "IQ1") (pin "1") (pinfunction "1_1") (pintype "input"))
      (node (ref "IR2") (pin "2") (pinfunction "2_2") (pintype "unspecified"))
    )
    (net (code "33") (name "Net-(IQ1-Pad3)") (class "Default")
      (node (ref "IQ1") (pin "3") (pinfunction "3_3") (pintype "input"))
      (node (ref "IR1") (pin "2") (pinfunction "2_2") (pintype "unspecified"))
    )
    (net (code "34") (name "Net-(IR-Pad2)") (class "Default")
      (node (ref "IR") (pin "2") (pinfunction "2_2") (pintype "unspecified"))
      (node (ref "IR1") (pin "1") (pinfunction "1_1") (pintype "unspecified"))
    )
    (net (code "35") (name "Net-(LCD_1-LVO_PIN3)") (class "Default")
      (node (ref "CONTRAST") (pin "2") (pinfunction "2_2") (pintype "input"))
      (node (ref "LCD_1") (pin "3") (pinfunction "LVO_PIN3_3") (pintype "unspecified"))
    )
    (net (code "36") (name "Net-(LCD_3-LBLA_PIN15)") (class "Default")
      (node (ref "LCD_3") (pin "1") (pinfunction "LBLA_PIN15_1") (pintype "unspecified"))
      (node (ref "LR1") (pin "2") (pinfunction "2_2") (pintype "unspecified"))
    )
    (net (code "37") (name "Net-(LCD_3-LBLK_PIN16)") (class "Default")
      (node (ref "LCD_3") (pin "2") (pinfunction "LBLK_PIN16_2") (pintype "unspecified"))
      (node (ref "LQ1") (pin "3") (pinfunction "3_3") (pintype "input"))
    )
    (net (code "38") (name "Net-(LQ1-Pad1)") (class "Default")
      (node (ref "LQ1") (pin "1") (pinfunction "1_1") (pintype "input"))
      (node (ref "LR2") (pin "2") (pinfunction "2_2") (pintype "unspecified"))
    )
    (net (code "39") (name "Net-(PD1-A)") (class "Default")
      (node (ref "PD1") (pin "2") (pinfunction "A_2") (pintype "unspecified"))
      (node (ref "PQ3") (pin "3") (pinfunction "D_3") (pintype "unspecified"))
      (node (ref "SPEAKER_LEFT") (pin "8") (pinfunction "8_8") (pintype "input"))
    )
    (net (code "40") (name "Net-(PD2-A)") (class "Default")
      (node (ref "PD2") (pin "2") (pinfunction "A_2") (pintype "unspecified"))
      (node (ref "PQ1") (pin "3") (pinfunction "D_3") (pintype "unspecified"))
      (node (ref "SPEAKER_RIGHT") (pin "8") (pinfunction "8_8") (pintype "input"))
    )
    (net (code "41") (name "Net-(POWER-+)") (class "Default")
      (node (ref "POWER") (pin "1") (pinfunction "+_1") (pintype "unspecified"))
      (node (ref "WC1") (pin "1") (pinfunction "1_1") (pintype "unspecified"))
      (node (ref "WC2") (pin "2") (pinfunction "2_2") (pintype "unspecified"))
      (node (ref "WU1") (pin "1") (pinfunction "INPUT_1") (pintype "unspecified"))
    )
    (net (code "42") (name "Net-(PQ1-G)") (class "Default")
      (node (ref "PQ1") (pin "1") (pinfunction "G_1") (pintype "unspecified"))
      (node (ref "PR1") (pin "2") (pinfunction "2_2") (pintype "unspecified"))
      (node (ref "PR2") (pin "1") (pinfunction "1_1") (pintype "unspecified"))
    )
    (net (code "43") (name "Net-(PQ2-Pad1)") (class "Default")
      (node (ref "PQ2") (pin "1") (pinfunction "1_1") (pintype "input"))
      (node (ref "PR3") (pin "2") (pinfunction "2_2") (pintype "unspecified"))
    )
    (net (code "44") (name "Net-(PQ3-G)") (class "Default")
      (node (ref "PQ3") (pin "1") (pinfunction "G_1") (pintype "unspecified"))
      (node (ref "PR5") (pin "2") (pinfunction "2_2") (pintype "unspecified"))
      (node (ref "PR6") (pin "1") (pinfunction "1_1") (pintype "unspecified"))
    )
    (net (code "45") (name "Net-(PQ4-B)") (class "Default")
      (node (ref "PQ4") (pin "1") (pinfunction "B_1") (pintype "unspecified"))
      (node (ref "PR9") (pin "2") (pinfunction "2_2") (pintype "unspecified"))
    )
    (net (code "46") (name "Net-(PQ4-C)") (class "Default")
      (node (ref "PQ4") (pin "3") (pinfunction "C_3") (pintype "unspecified"))
      (node (ref "SPEAKER_LED") (pin "4") (pinfunction "SPA_VCC_4") (pintype "unspecified"))
    )
    (net (code "47") (name "Net-(PQ5-Pad1)") (class "Default")
      (node (ref "PQ5") (pin "1") (pinfunction "1_1") (pintype "input"))
      (node (ref "PR11") (pin "2") (pinfunction "2_2") (pintype "unspecified"))
    )
    (net (code "48") (name "Net-(RXD-A)") (class "Default")
      (node (ref "ER1") (pin "1") (pinfunction "1_1") (pintype "unspecified"))
      (node (ref "RXD") (pin "2") (pinfunction "A_2") (pintype "unspecified"))
    )
    (net (code "49") (name "Net-(RXD-K)") (class "Default")
      (node (ref "EQ1") (pin "3") (pinfunction "3_3") (pintype "input"))
      (node (ref "RXD") (pin "1") (pinfunction "K_1") (pintype "unspecified"))
    )
    (net (code "50") (name "Net-(SD1-A)") (class "Default")
      (node (ref "SD1") (pin "2") (pinfunction "A_2") (pintype "unspecified"))
      (node (ref "SQ1") (pin "3") (pinfunction "D_3") (pintype "unspecified"))
      (node (ref "SUB") (pin "8") (pinfunction "8_8") (pintype "input"))
    )
    (net (code "51") (name "Net-(SPEAKER_LED-SPA_GND)") (class "Default")
      (node (ref "PR10") (pin "1") (pinfunction "1_1") (pintype "unspecified"))
      (node (ref "SPEAKER_LED") (pin "3") (pinfunction "SPA_GND_3") (pintype "unspecified"))
    )
    (net (code "52") (name "Net-(SPEAKER_LED-SPB_GND)") (class "Default")
      (node (ref "PQ5") (pin "3") (pinfunction "3_3") (pintype "input"))
      (node (ref "SPEAKER_LED") (pin "2") (pinfunction "SPB_GND_2") (pintype "unspecified"))
    )
    (net (code "53") (name "Net-(SPEAKER_LED-SPB_VCC)") (class "Default")
      (node (ref "PR8") (pin "1") (pinfunction "1_1") (pintype "unspecified"))
      (node (ref "SPEAKER_LED") (pin "1") (pinfunction "SPB_VCC_1") (pintype "unspecified"))
    )
    (net (code "54") (name "Net-(SPEAKER_RELAY_ON-A)") (class "Default")
      (node (ref "PR4") (pin "1") (pinfunction "1_1") (pintype "unspecified"))
      (node (ref "SPEAKER_RELAY_ON") (pin "2") (pinfunction "A_2") (pintype "unspecified"))
    )
    (net (code "55") (name "Net-(SPEAKER_RELAY_ON-K)") (class "Default")
      (node (ref "PQ2") (pin "3") (pinfunction "3_3") (pintype "input"))
      (node (ref "SPEAKER_RELAY_ON") (pin "1") (pinfunction "K_1") (pintype "unspecified"))
    )
    (net (code "56") (name "Net-(SQ1-G)") (class "Default")
      (node (ref "SQ1") (pin "1") (pinfunction "G_1") (pintype "unspecified"))
      (node (ref "SR1") (pin "1") (pinfunction "1_1") (pintype "unspecified"))
      (node (ref "SR2") (pin "2") (pinfunction "2_2") (pintype "unspecified"))
    )
    (net (code "57") (name "Net-(SQ2-Pad1)") (class "Default")
      (node (ref "SQ2") (pin "1") (pinfunction "1_1") (pintype "input"))
      (node (ref "SR6") (pin "2") (pinfunction "2_2") (pintype "unspecified"))
    )
    (net (code "58") (name "Net-(SQ3-Pad1)") (class "Default")
      (node (ref "SQ3") (pin "1") (pinfunction "1_1") (pintype "input"))
      (node (ref "SR7") (pin "2") (pinfunction "2_2") (pintype "unspecified"))
    )
    (net (code "59") (name "Net-(SQ4-B)") (class "Default")
      (node (ref "SQ4") (pin "1") (pinfunction "B_1") (pintype "unspecified"))
      (node (ref "SR8") (pin "2") (pinfunction "2_2") (pintype "unspecified"))
    )
    (net (code "60") (name "Net-(SQ4-C)") (class "Default")
      (node (ref "SQ4") (pin "3") (pinfunction "C_3") (pintype "unspecified"))
      (node (ref "SUB_LED") (pin "4") (pinfunction "SUBB_VCC_4") (pintype "unspecified"))
    )
    (net (code "61") (name "Net-(SUB_LED-SUBA_GND)") (class "Default")
      (node (ref "SQ2") (pin "3") (pinfunction "3_3") (pintype "input"))
      (node (ref "SUB_LED") (pin "2") (pinfunction "SUBA_GND_2") (pintype "unspecified"))
    )
    (net (code "62") (name "Net-(SUB_LED-SUBA_VCC)") (class "Default")
      (node (ref "SR3") (pin "1") (pinfunction "1_1") (pintype "unspecified"))
      (node (ref "SUB_LED") (pin "1") (pinfunction "SUBA_VCC_1") (pintype "unspecified"))
    )
    (net (code "63") (name "Net-(SUB_LED-SUBB_GND)") (class "Default")
      (node (ref "SR5") (pin "1") (pinfunction "1_1") (pintype "unspecified"))
      (node (ref "SUB_LED") (pin "3") (pinfunction "SUBB_GND_3") (pintype "unspecified"))
    )
    (net (code "64") (name "Net-(SUB_RELAY_ON-A)") (class "Default")
      (node (ref "SR4") (pin "1") (pinfunction "1_1") (pintype "unspecified"))
      (node (ref "SUB_RELAY_ON") (pin "2") (pinfunction "A_2") (pintype "unspecified"))
    )
    (net (code "65") (name "Net-(SUB_RELAY_ON-K)") (class "Default")
      (node (ref "SQ3") (pin "3") (pinfunction "3_3") (pintype "input"))
      (node (ref "SUB_RELAY_ON") (pin "1") (pinfunction "K_1") (pintype "unspecified"))
    )
    (net (code "66") (name "Net-(TO-Pad1)") (class "Default")
      (node (ref "TO") (pin "1") (pinfunction "1_1") (pintype "unspecified"))
      (node (ref "TR1") (pin "1") (pinfunction "1_1") (pintype "unspecified"))
    )
    (net (code "67") (name "Net-(TO-Pad2)") (class "Default")
      (node (ref "TO") (pin "2") (pinfunction "2_2") (pintype "unspecified"))
      (node (ref "TRIGGER") (pin "2") (pinfunction "2_2") (pintype "unspecified"))
    )
    (net (code "68") (name "Net-(TO-Pad3)") (class "Default")
      (node (ref "TO") (pin "3") (pinfunction "3_3") (pintype "unspecified"))
      (node (ref "TR2") (pin "2") (pinfunction "2_2") (pintype "unspecified"))
      (node (ref "TR4") (pin "1") (pinfunction "1_1") (pintype "unspecified"))
    )
    (net (code "69") (name "Net-(TQ-Pad1)") (class "Default")
      (node (ref "TQ") (pin "1") (pinfunction "1_1") (pintype "input"))
      (node (ref "TR4") (pin "2") (pinfunction "2_2") (pintype "unspecified"))
    )
    (net (code "70") (name "Net-(TR1-Pad2)") (class "Default")
      (node (ref "TR1") (pin "2") (pinfunction "2_2") (pintype "unspecified"))
      (node (ref "TRIGGER") (pin "1") (pinfunction "1_1") (pintype "unspecified"))
    )
    (net (code "71") (name "Net-(TXD-A)") (class "Default")
      (node (ref "ER3") (pin "1") (pinfunction "1_1") (pintype "unspecified"))
      (node (ref "TXD") (pin "2") (pinfunction "A_2") (pintype "unspecified"))
    )
    (net (code "72") (name "Net-(TXD-K)") (class "Default")
      (node (ref "EQ2") (pin "3") (pinfunction "3_3") (pintype "input"))
      (node (ref "TXD") (pin "1") (pinfunction "K_1") (pintype "unspecified"))
    )
    (net (code "73") (name "Net-(YAMAHA_TRIGGER_ON-A)") (class "Default")
      (node (ref "TR3") (pin "1") (pinfunction "1_1") (pintype "unspecified"))
      (node (ref "YAMAHA_TRIGGER_ON") (pin "2") (pinfunction "A_2") (pintype "unspecified"))
    )
    (net (code "74") (name "Net-(YAMAHA_TRIGGER_ON-K)") (class "Default")
      (node (ref "TQ") (pin "3") (pinfunction "3_3") (pintype "input"))
      (node (ref "YAMAHA_TRIGGER_ON") (pin "1") (pinfunction "K_1") (pintype "unspecified"))
    )
    (net (code "75") (name "RESET") (class "Default")
      (node (ref "AR1") (pin "1") (pinfunction "1_1") (pintype "unspecified"))
      (node (ref "AT1") (pin "29") (pinfunction "PC6(RESET#/PCINT14)_29") (pintype "unspecified"))
      (node (ref "EC1") (pin "2") (pinfunction "2_2") (pintype "input"))
      (node (ref "RESET1") (pin "1") (pinfunction "1_1") (pintype "unspecified"))
    )
    (net (code "76") (name "RIGHT_IN_CAM_BLACK") (class "Default")
      (node (ref "SPEAKER_RIGHT") (pin "4") (pinfunction "4_4") (pintype "input"))
      (node (ref "U1") (pin "17") (pinfunction "17_17") (pintype "unspecified"))
    )
    (net (code "77") (name "RIGHT_IN_CAM_RED") (class "Default")
      (node (ref "SPEAKER_RIGHT") (pin "5") (pinfunction "5_5") (pintype "input"))
      (node (ref "U1") (pin "19") (pinfunction "19_19") (pintype "unspecified"))
    )
    (net (code "78") (name "RIGHT_IN_YAM_BLACK") (class "Default")
      (node (ref "SPEAKER_RIGHT") (pin "2") (pinfunction "2_2") (pintype "input"))
      (node (ref "U1") (pin "18") (pinfunction "18_18") (pintype "unspecified"))
    )
    (net (code "79") (name "RIGHT_IN_YAM_RED") (class "Default")
      (node (ref "SPEAKER_RIGHT") (pin "7") (pinfunction "7_7") (pintype "input"))
      (node (ref "U1") (pin "20") (pinfunction "20_20") (pintype "unspecified"))
    )
    (net (code "80") (name "RIGHT_OUT_BLACK") (class "Default")
      (node (ref "SPEAKER_RIGHT") (pin "3") (pinfunction "3_3") (pintype "input"))
      (node (ref "U1") (pin "14") (pinfunction "14_14") (pintype "unspecified"))
    )
    (net (code "81") (name "RIGHT_OUT_RED") (class "Default")
      (node (ref "SPEAKER_RIGHT") (pin "6") (pinfunction "6_6") (pintype "input"))
      (node (ref "U1") (pin "12") (pinfunction "12_12") (pintype "unspecified"))
    )
    (net (code "82") (name "SUB_CAM_OUT_GND") (class "Default")
      (node (ref "SUB") (pin "7") (pinfunction "7_7") (pintype "input"))
      (node (ref "U1") (pin "5") (pinfunction "5_5") (pintype "unspecified"))
    )
    (net (code "83") (name "SUB_CAM_OUT_TIP") (class "Default")
      (node (ref "SUB") (pin "4") (pinfunction "4_4") (pintype "input"))
      (node (ref "U1") (pin "1") (pinfunction "1_1") (pintype "unspecified"))
    )
    (net (code "84") (name "SUB_IN_GND") (class "Default")
      (node (ref "SUB") (pin "6") (pinfunction "6_6") (pintype "input"))
      (node (ref "U1") (pin "4") (pinfunction "4_4") (pintype "unspecified"))
    )
    (net (code "85") (name "SUB_IN_TIP") (class "Default")
      (node (ref "SUB") (pin "3") (pinfunction "3_3") (pintype "input"))
      (node (ref "U1") (pin "2") (pinfunction "2_2") (pintype "unspecified"))
    )
    (net (code "86") (name "SUB_YAM_OUT_GND") (class "Default")
      (node (ref "SUB") (pin "5") (pinfunction "5_5") (pintype "input"))
      (node (ref "U1") (pin "3") (pinfunction "3_3") (pintype "unspecified"))
    )
    (net (code "87") (name "SUB_YAM_OUT_TIP") (class "Default")
      (node (ref "SUB") (pin "2") (pinfunction "2_2") (pintype "input"))
      (node (ref "U1") (pin "7") (pinfunction "7_7") (pintype "unspecified"))
    )
    (net (code "88") (name "VCC") (class "Default")
      (node (ref "AC1") (pin "1") (pinfunction "1_1") (pintype "input"))
      (node (ref "AC2") (pin "1") (pinfunction "1_1") (pintype "input"))
      (node (ref "AR1") (pin "2") (pinfunction "2_2") (pintype "unspecified"))
      (node (ref "AT1") (pin "18") (pinfunction "AVCC_18") (pintype "unspecified"))
      (node (ref "AT1") (pin "4") (pinfunction "VCC_4") (pintype "unspecified"))
      (node (ref "AT1") (pin "6") (pinfunction "VCC_6") (pintype "unspecified"))
      (node (ref "BRIGHTNESS") (pin "3") (pinfunction "3_3") (pintype "input"))
      (node (ref "CONTRAST") (pin "1") (pinfunction "1_1") (pintype "input"))
      (node (ref "ER1") (pin "2") (pinfunction "2_2") (pintype "unspecified"))
      (node (ref "ER3") (pin "2") (pinfunction "2_2") (pintype "unspecified"))
      (node (ref "IR") (pin "1") (pinfunction "1_1") (pintype "unspecified"))
      (node (ref "LCD_1") (pin "2") (pinfunction "LDD_PIN2_2") (pintype "unspecified"))
      (node (ref "LR1") (pin "1") (pinfunction "1_1") (pintype "unspecified"))
      (node (ref "PD1") (pin "1") (pinfunction "C_1") (pintype "unspecified"))
      (node (ref "PD2") (pin "1") (pinfunction "C_1") (pintype "unspecified"))
      (node (ref "PQ4") (pin "2") (pinfunction "E_2") (pintype "unspecified"))
      (node (ref "PR4") (pin "2") (pinfunction "2_2") (pintype "unspecified"))
      (node (ref "PR8") (pin "2") (pinfunction "2_2") (pintype "unspecified"))
      (node (ref "SD1") (pin "1") (pinfunction "C_1") (pintype "unspecified"))
      (node (ref "SPEAKER_LEFT") (pin "1") (pinfunction "1_1") (pintype "input"))
      (node (ref "SPEAKER_RIGHT") (pin "1") (pinfunction "1_1") (pintype "input"))
      (node (ref "SQ4") (pin "2") (pinfunction "E_2") (pintype "unspecified"))
      (node (ref "SR3") (pin "2") (pinfunction "2_2") (pintype "unspecified"))
      (node (ref "SR4") (pin "2") (pinfunction "2_2") (pintype "unspecified"))
      (node (ref "SUB") (pin "1") (pinfunction "1_1") (pintype "input"))
      (node (ref "TO") (pin "4") (pinfunction "4_4") (pintype "unspecified"))
      (node (ref "TR3") (pin "2") (pinfunction "2_2") (pintype "unspecified"))
      (node (ref "WC3") (pin "2") (pinfunction "2_2") (pintype "unspecified"))
      (node (ref "WC4") (pin "2") (pinfunction "2_2") (pintype "unspecified"))
      (node (ref "WU1") (pin "3") (pinfunction "OUTPUT_3") (pintype "unspecified"))
    )
    (net (code "89") (name "unconnected-(AT1-ADC6-Pad19)") (class "Default")
      (node (ref "AT1") (pin "19") (pinfunction "ADC6_19") (pintype "unspecified"))
    )
    (net (code "90") (name "unconnected-(AT1-ADC7-Pad22)") (class "Default")
      (node (ref "AT1") (pin "22") (pinfunction "ADC7_22") (pintype "unspecified"))
    )
    (net (code "91") (name "unconnected-(AT1-AREF-Pad20)") (class "Default")
      (node (ref "AT1") (pin "20") (pinfunction "AREF_20") (pintype "unspecified"))
    )
    (net (code "92") (name "unconnected-(AT1-PB5(SCK{slash}PCINT5)-Pad17)") (class "Default")
      (node (ref "AT1") (pin "17") (pinfunction "PB5(SCK/PCINT5)_17") (pintype "unspecified"))
    )
    (net (code "93") (name "unconnected-(AX1-GND-Pad2)") (class "Default")
      (node (ref "AX1") (pin "2") (pinfunction "GND_2") (pintype "input"))
    )
    (net (code "94") (name "unconnected-(MB_CANC-Pad2)") (class "Default")
      (node (ref "MB_CANC") (pin "2") (pinfunction "2_2") (pintype "unspecified"))
    )
    (net (code "95") (name "unconnected-(MB_CANC-Pad3)") (class "Default")
      (node (ref "MB_CANC") (pin "3") (pinfunction "3_3") (pintype "unspecified"))
    )
    (net (code "96") (name "unconnected-(MB_MENU-Pad2)") (class "Default")
      (node (ref "MB_MENU") (pin "2") (pinfunction "2_2") (pintype "unspecified"))
    )
    (net (code "97") (name "unconnected-(MB_MENU-Pad3)") (class "Default")
      (node (ref "MB_MENU") (pin "3") (pinfunction "3_3") (pintype "unspecified"))
    )
    (net (code "98") (name "unconnected-(MB_OK-Pad2)") (class "Default")
      (node (ref "MB_OK") (pin "2") (pinfunction "2_2") (pintype "unspecified"))
    )
    (net (code "99") (name "unconnected-(MB_OK-Pad3)") (class "Default")
      (node (ref "MB_OK") (pin "3") (pinfunction "3_3") (pintype "unspecified"))
    )
    (net (code "100") (name "unconnected-(RESET1-Pad2)") (class "Default")
      (node (ref "RESET1") (pin "2") (pinfunction "2_2") (pintype "unspecified"))
    )
    (net (code "101") (name "unconnected-(RESET1-Pad3)") (class "Default")
      (node (ref "RESET1") (pin "3") (pinfunction "3_3") (pintype "unspecified"))
    )
    (net (code "102") (name "unconnected-(SERIAL-Pad2)") (class "Default")
      (node (ref "SERIAL") (pin "2") (pinfunction "2_2") (pintype "unspecified"))
    )
    (net (code "103") (name "unconnected-(SERIAL-Pad3)") (class "Default")
      (node (ref "SERIAL") (pin "3") (pinfunction "3_3") (pintype "unspecified"))
    )
    (net (code "104") (name "unconnected-(U1-Pad6)") (class "Default")
      (node (ref "U1") (pin "6") (pinfunction "6_6") (pintype "unspecified"))
    )
    (net (code "105") (name "unconnected-(U1-Pad8)") (class "Default")
      (node (ref "U1") (pin "8") (pinfunction "8_8") (pintype "unspecified"))
    )
    (net (code "106") (name "unconnected-(U1-Pad9)") (class "Default")
      (node (ref "U1") (pin "9") (pinfunction "9_9") (pintype "unspecified"))
    )
    (net (code "107") (name "unconnected-(U1-Pad10)") (class "Default")
      (node (ref "U1") (pin "10") (pinfunction "10_10") (pintype "unspecified"))
    )
    (net (code "108") (name "unconnected-(U1-Pad15)") (class "Default")
      (node (ref "U1") (pin "15") (pinfunction "15_15") (pintype "unspecified"))
    )
    (net (code "109") (name "unconnected-(U1-Pad16)") (class "Default")
      (node (ref "U1") (pin "16") (pinfunction "16_16") (pintype "unspecified"))
    )
  )
)
